# or-clock_main.net
KiCad netlist of a schematic drawn in EAGLE
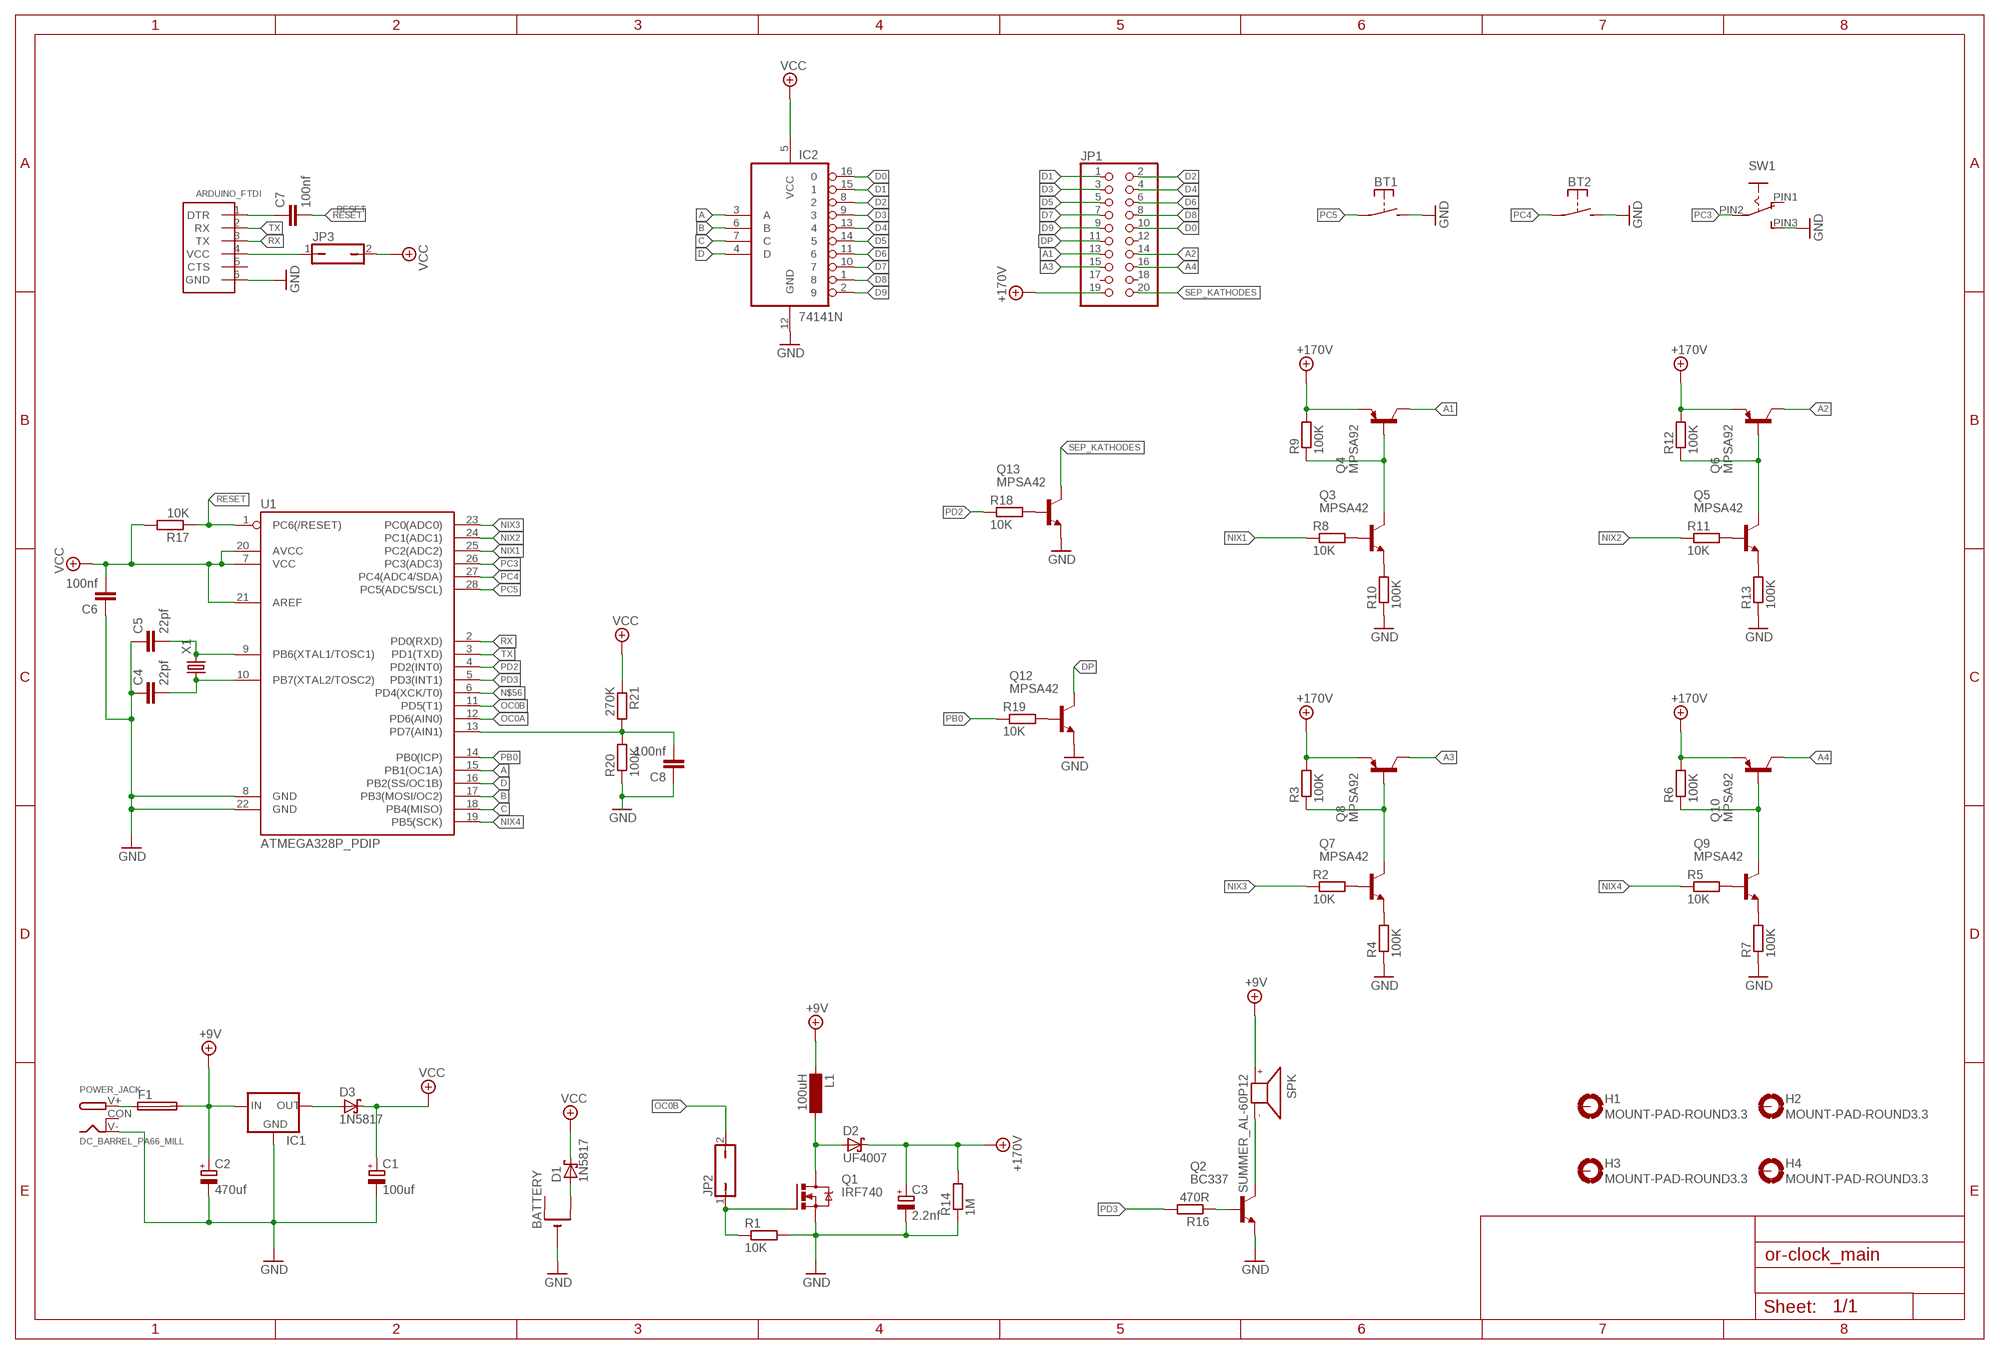
[diagram p0: schematic, sheet 1]

(export (version "E")
  (design (tool "Eeschema 10.0.6"))
  (components
    (comp (ref "BATTERY")
      (value "CR1220THM")
      (footprint "eagle-import:CR1220-THM")
      (libsource (lib "eagle-import") (part "CR1220THM"))
    )
    (comp (ref "BT1")
      (value "SWITCH_3305D")
      (footprint "eagle-import:BUT3305D")
      (libsource (lib "eagle-import") (part "SWITCH_3305D"))
    )
    (comp (ref "BT2")
      (value "SWITCH_3305D")
      (footprint "eagle-import:BUT3305D")
      (libsource (lib "eagle-import") (part "SWITCH_3305D"))
    )
    (comp (ref "C1")
      (value "100uf")
      (footprint "eagle-import:E5-6")
      (libsource (lib "eagle-import") (part "CPOL-EUE5-6"))
    )
    (comp (ref "C2")
      (value "470uf")
      (footprint "eagle-import:E5-10,5")
      (libsource (lib "eagle-import") (part "CPOL-EUE5-10.5"))
    )
    (comp (ref "C3")
      (value "2.2nf")
      (footprint "eagle-import:E5-8,5")
      (libsource (lib "eagle-import") (part "CPOL-EUE5-8.5"))
    )
    (comp (ref "C4")
      (value "22pf")
      (footprint "eagle-import:C025-025X050")
      (libsource (lib "eagle-import") (part "C-EU025-025X050"))
    )
    (comp (ref "C5")
      (value "22pf")
      (footprint "eagle-import:C025-025X050")
      (libsource (lib "eagle-import") (part "C-EU025-025X050"))
    )
    (comp (ref "C6")
      (value "100nf")
      (footprint "eagle-import:C025-025X050")
      (libsource (lib "eagle-import") (part "C-EU025-025X050"))
    )
    (comp (ref "C7")
      (value "100nf")
      (footprint "eagle-import:C025-025X050")
      (libsource (lib "eagle-import") (part "C-EU025-025X050"))
    )
    (comp (ref "C8")
      (value "100nf")
      (footprint "eagle-import:C025-025X050")
      (libsource (lib "eagle-import") (part "C-EU025-025X050"))
    )
    (comp (ref "D1")
      (value "1N5817")
      (footprint "eagle-import:DO41-7.6")
      (libsource (lib "eagle-import") (part "1N5817-B"))
    )
    (comp (ref "D2")
      (value "UF4007")
      (footprint "eagle-import:DO41-7.6")
      (libsource (lib "eagle-import") (part "1N5817-B"))
    )
    (comp (ref "D3")
      (value "1N5817")
      (footprint "eagle-import:DO41-7.6")
      (libsource (lib "eagle-import") (part "1N5817-B"))
    )
    (comp (ref "F1")
      (value "LITTLEFUSE")
      (footprint "eagle-import:LITTLEFUSE")
      (libsource (lib "eagle-import") (part "LITTLEFUSE"))
    )
    (comp (ref "H1")
      (value "MOUNT-PAD-ROUND3.3")
      (footprint "eagle-import:3,3-PAD")
      (libsource (lib "eagle-import") (part "MOUNT-PAD-ROUND3.3"))
    )
    (comp (ref "H2")
      (value "MOUNT-PAD-ROUND3.3")
      (footprint "eagle-import:3,3-PAD")
      (libsource (lib "eagle-import") (part "MOUNT-PAD-ROUND3.3"))
    )
    (comp (ref "H3")
      (value "MOUNT-PAD-ROUND3.3")
      (footprint "eagle-import:3,3-PAD")
      (libsource (lib "eagle-import") (part "MOUNT-PAD-ROUND3.3"))
    )
    (comp (ref "H4")
      (value "MOUNT-PAD-ROUND3.3")
      (footprint "eagle-import:3,3-PAD")
      (libsource (lib "eagle-import") (part "MOUNT-PAD-ROUND3.3"))
    )
    (comp (ref "IC1")
      (value "78XXS")
      (footprint "eagle-import:78XXS")
      (libsource (lib "eagle-import") (part "78XXS"))
    )
    (comp (ref "IC2")
      (value "74141N")
      (footprint "eagle-import:DIL16")
      (libsource (lib "eagle-import") (part "74141N"))
    )
    (comp (ref "JP1")
      (value "PINHD-2X10_FEMALE")
      (footprint "eagle-import:2X10")
      (libsource (lib "eagle-import") (part "PINHD-2X10_FEMALE"))
    )
    (comp (ref "JP2")
      (value "JP1Q")
      (footprint "eagle-import:JP1")
      (libsource (lib "eagle-import") (part "JP1Q"))
    )
    (comp (ref "JP3")
      (value "JP1Q")
      (footprint "eagle-import:JP1")
      (libsource (lib "eagle-import") (part "JP1Q"))
    )
    (comp (ref "L1")
      (value "100uH")
      (footprint "eagle-import:BS11")
      (libsource (lib "eagle-import") (part "BS11"))
    )
    (comp (ref "POWER_JACK")
      (value "DC_BARREL_PA66_MILL")
      (footprint "eagle-import:PA66_DC_JACK_MILL")
      (libsource (lib "eagle-import") (part "DC_BARREL_PA66_MILL"))
    )
    (comp (ref "Q1")
      (value "IRF740")
      (footprint "eagle-import:TO220BV")
      (libsource (lib "eagle-import") (part "IRF740"))
    )
    (comp (ref "Q2")
      (value "BC337")
      (footprint "eagle-import:TO92-")
      (libsource (lib "eagle-import") (part "BC547TO92_STRAIT"))
    )
    (comp (ref "Q3")
      (value "MPSA42")
      (footprint "eagle-import:TO92-")
      (libsource (lib "eagle-import") (part "MPSA42"))
    )
    (comp (ref "Q4")
      (value "MPSA92")
      (footprint "eagle-import:TO92-")
      (libsource (lib "eagle-import") (part "MPSA92"))
    )
    (comp (ref "Q5")
      (value "MPSA42")
      (footprint "eagle-import:TO92-")
      (libsource (lib "eagle-import") (part "MPSA42"))
    )
    (comp (ref "Q6")
      (value "MPSA92")
      (footprint "eagle-import:TO92-")
      (libsource (lib "eagle-import") (part "MPSA92"))
    )
    (comp (ref "Q7")
      (value "MPSA42")
      (footprint "eagle-import:TO92-")
      (libsource (lib "eagle-import") (part "MPSA42"))
    )
    (comp (ref "Q8")
      (value "MPSA92")
      (footprint "eagle-import:TO92-")
      (libsource (lib "eagle-import") (part "MPSA92"))
    )
    (comp (ref "Q9")
      (value "MPSA42")
      (footprint "eagle-import:TO92-")
      (libsource (lib "eagle-import") (part "MPSA42"))
    )
    (comp (ref "Q10")
      (value "MPSA92")
      (footprint "eagle-import:TO92-")
      (libsource (lib "eagle-import") (part "MPSA92"))
    )
    (comp (ref "Q12")
      (value "MPSA42")
      (footprint "eagle-import:TO92-")
      (libsource (lib "eagle-import") (part "MPSA42"))
    )
    (comp (ref "Q13")
      (value "MPSA42")
      (footprint "eagle-import:TO92-")
      (libsource (lib "eagle-import") (part "MPSA42"))
    )
    (comp (ref "R1")
      (value "10K")
      (footprint "eagle-import:0207_2V")
      (libsource (lib "eagle-import") (part "R-EU_0207/2V"))
    )
    (comp (ref "R2")
      (value "10K")
      (footprint "eagle-import:0207_2V")
      (libsource (lib "eagle-import") (part "R-EU_0207/2V"))
    )
    (comp (ref "R3")
      (value "100K")
      (footprint "eagle-import:0207_2V")
      (libsource (lib "eagle-import") (part "R-EU_0207/2V"))
    )
    (comp (ref "R4")
      (value "100K")
      (footprint "eagle-import:0207_2V")
      (libsource (lib "eagle-import") (part "R-EU_0207/2V"))
    )
    (comp (ref "R5")
      (value "10K")
      (footprint "eagle-import:0207_2V")
      (libsource (lib "eagle-import") (part "R-EU_0207/2V"))
    )
    (comp (ref "R6")
      (value "100K")
      (footprint "eagle-import:0207_2V")
      (libsource (lib "eagle-import") (part "R-EU_0207/2V"))
    )
    (comp (ref "R7")
      (value "100K")
      (footprint "eagle-import:0207_2V")
      (libsource (lib "eagle-import") (part "R-EU_0207/2V"))
    )
    (comp (ref "R8")
      (value "10K")
      (footprint "eagle-import:0207_2V")
      (libsource (lib "eagle-import") (part "R-EU_0207/2V"))
    )
    (comp (ref "R9")
      (value "100K")
      (footprint "eagle-import:0207_2V")
      (libsource (lib "eagle-import") (part "R-EU_0207/2V"))
    )
    (comp (ref "R10")
      (value "100K")
      (footprint "eagle-import:0207_2V")
      (libsource (lib "eagle-import") (part "R-EU_0207/2V"))
    )
    (comp (ref "R11")
      (value "10K")
      (footprint "eagle-import:0207_2V")
      (libsource (lib "eagle-import") (part "R-EU_0207/2V"))
    )
    (comp (ref "R12")
      (value "100K")
      (footprint "eagle-import:0207_2V")
      (libsource (lib "eagle-import") (part "R-EU_0207/2V"))
    )
    (comp (ref "R13")
      (value "100K")
      (footprint "eagle-import:0207_2V")
      (libsource (lib "eagle-import") (part "R-EU_0207/2V"))
    )
    (comp (ref "R14")
      (value "1M")
      (footprint "eagle-import:0207_7")
      (libsource (lib "eagle-import") (part "R-EU_0207/7"))
    )
    (comp (ref "R16")
      (value "470R")
      (footprint "eagle-import:0207_2V")
      (libsource (lib "eagle-import") (part "R-EU_0207/2V"))
    )
    (comp (ref "R17")
      (value "10K")
      (footprint "eagle-import:0207_2V")
      (libsource (lib "eagle-import") (part "R-EU_0207/2V"))
    )
    (comp (ref "R18")
      (value "10K")
      (footprint "eagle-import:0207_2V")
      (libsource (lib "eagle-import") (part "R-EU_0207/2V"))
    )
    (comp (ref "R19")
      (value "10K")
      (footprint "eagle-import:0207_2V")
      (libsource (lib "eagle-import") (part "R-EU_0207/2V"))
    )
    (comp (ref "R20")
      (value "100K")
      (footprint "eagle-import:0207_2V")
      (libsource (lib "eagle-import") (part "R-EU_0207/2V"))
    )
    (comp (ref "R21")
      (value "270K")
      (footprint "eagle-import:0207_2V")
      (libsource (lib "eagle-import") (part "R-EU_0207/2V"))
    )
    (comp (ref "SERIAL_CON")
      (value "ARDUINO_FTDI_HEADERV")
      (footprint "eagle-import:1X06")
      (libsource (lib "eagle-import") (part "ARDUINO_FTDI_HEADERV"))
    )
    (comp (ref "SPK")
      (value "SUMMER_AL-60P12")
      (footprint "eagle-import:AL-60P12_SUMMER")
      (libsource (lib "eagle-import") (part "SUMMER_AL-60P12"))
    )
    (comp (ref "SW1")
      (value "13P_SW")
      (footprint "eagle-import:TS-13P")
      (libsource (lib "eagle-import") (part "13P_SW"))
    )
    (comp (ref "U1")
      (value "ATMEGA328P_PDIP")
      (footprint "eagle-import:DIL28-3")
      (libsource (lib "eagle-import") (part "ATMEGA328P_PDIP"))
    )
    (comp (ref "X1")
      (value "CRYSTALTC26V")
      (footprint "eagle-import:TC26V")
      (libsource (lib "eagle-import") (part "CRYSTALTC26V"))
    )
  )
  (nets
    (net (code "1") (name "+9V") (class "Default")
      (node (ref "C2") (pin "+") (pinfunction "+_+") (pintype "passive"))
      (node (ref "F1") (pin "2") (pinfunction "2_2") (pintype "passive"))
      (node (ref "IC1") (pin "IN") (pinfunction "IN_IN") (pintype "input"))
      (node (ref "L1") (pin "1") (pinfunction "1_1") (pintype "passive"))
      (node (ref "SPK") (pin "POS") (pinfunction "+_POS") (pintype "passive"))
    )
    (net (code "2") (name "+170V") (class "Default")
      (node (ref "C3") (pin "+") (pinfunction "+_+") (pintype "passive"))
      (node (ref "D2") (pin "C") (pinfunction "C_C") (pintype "passive"))
      (node (ref "JP1") (pin "19") (pinfunction "19_19") (pintype "passive"))
      (node (ref "Q10") (pin "3") (pinfunction "E_3") (pintype "passive"))
      (node (ref "Q4") (pin "3") (pinfunction "E_3") (pintype "passive"))
      (node (ref "Q6") (pin "3") (pinfunction "E_3") (pintype "passive"))
      (node (ref "Q8") (pin "3") (pinfunction "E_3") (pintype "passive"))
      (node (ref "R12") (pin "2") (pinfunction "2_2") (pintype "passive"))
      (node (ref "R14") (pin "2") (pinfunction "2_2") (pintype "passive"))
      (node (ref "R3") (pin "2") (pinfunction "2_2") (pintype "passive"))
      (node (ref "R6") (pin "2") (pinfunction "2_2") (pintype "passive"))
      (node (ref "R9") (pin "2") (pinfunction "2_2") (pintype "passive"))
    )
    (net (code "3") (name "/GNDBREAK") (class "Default")
      (node (ref "POWER_JACK") (pin "CON") (pinfunction "GNDBREAK_CON") (pintype "power_in"))
    )
    (net (code "4") (name "A") (class "Default")
      (node (ref "IC2") (pin "3") (pinfunction "A_3") (pintype "input"))
      (node (ref "U1") (pin "15") (pinfunction "PB1(OC1A)_15") (pintype "bidirectional"))
    )
    (net (code "5") (name "A1") (class "Default")
      (node (ref "JP1") (pin "13") (pinfunction "13_13") (pintype "passive"))
      (node (ref "Q4") (pin "1") (pinfunction "C_1") (pintype "passive"))
    )
    (net (code "6") (name "A2") (class "Default")
      (node (ref "JP1") (pin "14") (pinfunction "14_14") (pintype "passive"))
      (node (ref "Q6") (pin "1") (pinfunction "C_1") (pintype "passive"))
    )
    (net (code "7") (name "A3") (class "Default")
      (node (ref "JP1") (pin "15") (pinfunction "15_15") (pintype "passive"))
      (node (ref "Q8") (pin "1") (pinfunction "C_1") (pintype "passive"))
    )
    (net (code "8") (name "A4") (class "Default")
      (node (ref "JP1") (pin "16") (pinfunction "16_16") (pintype "passive"))
      (node (ref "Q10") (pin "1") (pinfunction "C_1") (pintype "passive"))
    )
    (net (code "9") (name "B") (class "Default")
      (node (ref "IC2") (pin "6") (pinfunction "B_6") (pintype "input"))
      (node (ref "U1") (pin "17") (pinfunction "PB3(MOSI/OC2)_17") (pintype "bidirectional"))
    )
    (net (code "10") (name "C") (class "Default")
      (node (ref "IC2") (pin "7") (pinfunction "C_7") (pintype "input"))
      (node (ref "U1") (pin "18") (pinfunction "PB4(MISO)_18") (pintype "bidirectional"))
    )
    (net (code "11") (name "D") (class "Default")
      (node (ref "IC2") (pin "4") (pinfunction "D_4") (pintype "input"))
      (node (ref "U1") (pin "16") (pinfunction "PB2(SS/OC1B)_16") (pintype "bidirectional"))
    )
    (net (code "12") (name "D0") (class "Default")
      (node (ref "IC2") (pin "16") (pinfunction "0_16") (pintype "open_collector"))
      (node (ref "JP1") (pin "10") (pinfunction "10_10") (pintype "passive"))
    )
    (net (code "13") (name "D1") (class "Default")
      (node (ref "IC2") (pin "15") (pinfunction "1_15") (pintype "open_collector"))
      (node (ref "JP1") (pin "1") (pinfunction "1_1") (pintype "passive"))
    )
    (net (code "14") (name "D2") (class "Default")
      (node (ref "IC2") (pin "8") (pinfunction "2_8") (pintype "open_collector"))
      (node (ref "JP1") (pin "2") (pinfunction "2_2") (pintype "passive"))
    )
    (net (code "15") (name "D3") (class "Default")
      (node (ref "IC2") (pin "9") (pinfunction "3_9") (pintype "open_collector"))
      (node (ref "JP1") (pin "3") (pinfunction "3_3") (pintype "passive"))
    )
    (net (code "16") (name "D4") (class "Default")
      (node (ref "IC2") (pin "13") (pinfunction "4_13") (pintype "open_collector"))
      (node (ref "JP1") (pin "4") (pinfunction "4_4") (pintype "passive"))
    )
    (net (code "17") (name "D5") (class "Default")
      (node (ref "IC2") (pin "14") (pinfunction "5_14") (pintype "open_collector"))
      (node (ref "JP1") (pin "5") (pinfunction "5_5") (pintype "passive"))
    )
    (net (code "18") (name "D6") (class "Default")
      (node (ref "IC2") (pin "11") (pinfunction "6_11") (pintype "open_collector"))
      (node (ref "JP1") (pin "6") (pinfunction "6_6") (pintype "passive"))
    )
    (net (code "19") (name "D7") (class "Default")
      (node (ref "IC2") (pin "10") (pinfunction "7_10") (pintype "open_collector"))
      (node (ref "JP1") (pin "7") (pinfunction "7_7") (pintype "passive"))
    )
    (net (code "20") (name "D8") (class "Default")
      (node (ref "IC2") (pin "1") (pinfunction "8_1") (pintype "open_collector"))
      (node (ref "JP1") (pin "8") (pinfunction "8_8") (pintype "passive"))
    )
    (net (code "21") (name "D9") (class "Default")
      (node (ref "IC2") (pin "2") (pinfunction "9_2") (pintype "open_collector"))
      (node (ref "JP1") (pin "9") (pinfunction "9_9") (pintype "passive"))
    )
    (net (code "22") (name "DP") (class "Default")
      (node (ref "JP1") (pin "11") (pinfunction "11_11") (pintype "passive"))
      (node (ref "Q12") (pin "1") (pinfunction "C_1") (pintype "passive"))
    )
    (net (code "23") (name "GND") (class "Default")
      (node (ref "BATTERY") (pin "-") (pinfunction "-_-") (pintype "passive"))
      (node (ref "BT1") (pin "P$2") (pinfunction "S_P$2") (pintype "passive"))
      (node (ref "BT2") (pin "P$2") (pinfunction "S_P$2") (pintype "passive"))
      (node (ref "C1") (pin "-") (pinfunction "-_-") (pintype "passive"))
      (node (ref "C2") (pin "-") (pinfunction "-_-") (pintype "passive"))
      (node (ref "C3") (pin "-") (pinfunction "-_-") (pintype "passive"))
      (node (ref "C4") (pin "1") (pinfunction "1_1") (pintype "passive"))
      (node (ref "C5") (pin "1") (pinfunction "1_1") (pintype "passive"))
      (node (ref "C6") (pin "1") (pinfunction "1_1") (pintype "passive"))
      (node (ref "C8") (pin "1") (pinfunction "1_1") (pintype "passive"))
      (node (ref "IC1") (pin "GND") (pinfunction "GND_GND") (pintype "input"))
      (node (ref "IC2") (pin "12") (pinfunction "GND_12") (pintype "power_in"))
      (node (ref "POWER_JACK") (pin "V-") (pinfunction "GND_V-") (pintype "power_in"))
      (node (ref "Q1") (pin "S") (pinfunction "S_S") (pintype "passive"))
      (node (ref "Q12") (pin "3") (pinfunction "E_3") (pintype "passive"))
      (node (ref "Q13") (pin "3") (pinfunction "E_3") (pintype "passive"))
      (node (ref "Q2") (pin "1") (pinfunction "E_1") (pintype "passive"))
      (node (ref "R1") (pin "2") (pinfunction "2_2") (pintype "passive"))
      (node (ref "R10") (pin "1") (pinfunction "1_1") (pintype "passive"))
      (node (ref "R13") (pin "1") (pinfunction "1_1") (pintype "passive"))
      (node (ref "R14") (pin "1") (pinfunction "1_1") (pintype "passive"))
      (node (ref "R20") (pin "1") (pinfunction "1_1") (pintype "passive"))
      (node (ref "R4") (pin "1") (pinfunction "1_1") (pintype "passive"))
      (node (ref "R7") (pin "1") (pinfunction "1_1") (pintype "passive"))
      (node (ref "SERIAL_CON") (pin "6") (pinfunction "GND_6") (pintype "bidirectional"))
      (node (ref "SW1") (pin "PIN3") (pinfunction "S_PIN3") (pintype "passive"))
      (node (ref "U1") (pin "22") (pinfunction "GND_22") (pintype "bidirectional"))
      (node (ref "U1") (pin "8") (pinfunction "GND_8") (pintype "bidirectional"))
    )
    (net (code "24") (name "N$56") (class "Default")
      (node (ref "U1") (pin "6") (pinfunction "PD4(XCK/T0)_6") (pintype "bidirectional"))
    )
    (net (code "25") (name "NIX1") (class "Default")
      (node (ref "R8") (pin "1") (pinfunction "1_1") (pintype "passive"))
      (node (ref "U1") (pin "25") (pinfunction "PC2(ADC2)_25") (pintype "bidirectional"))
    )
    (net (code "26") (name "NIX2") (class "Default")
      (node (ref "R11") (pin "1") (pinfunction "1_1") (pintype "passive"))
      (node (ref "U1") (pin "24") (pinfunction "PC1(ADC1)_24") (pintype "bidirectional"))
    )
    (net (code "27") (name "NIX3") (class "Default")
      (node (ref "R2") (pin "1") (pinfunction "1_1") (pintype "passive"))
      (node (ref "U1") (pin "23") (pinfunction "PC0(ADC0)_23") (pintype "bidirectional"))
    )
    (net (code "28") (name "NIX4") (class "Default")
      (node (ref "R5") (pin "1") (pinfunction "1_1") (pintype "passive"))
      (node (ref "U1") (pin "19") (pinfunction "PB5(SCK)_19") (pintype "bidirectional"))
    )
    (net (code "29") (name "Net-(BATTERY-+1)") (class "Default")
      (node (ref "BATTERY") (pin "+2") (pinfunction "+1_+2") (pintype "passive"))
      (node (ref "D1") (pin "A") (pinfunction "A_A") (pintype "passive"))
    )
    (net (code "30") (name "Net-(D2-PadA)") (class "Default")
      (node (ref "D2") (pin "A") (pinfunction "A_A") (pintype "passive"))
      (node (ref "L1") (pin "2") (pinfunction "2_2") (pintype "passive"))
      (node (ref "Q1") (pin "D") (pinfunction "D_D") (pintype "passive"))
    )
    (net (code "31") (name "Net-(D3-PadA)") (class "Default")
      (node (ref "D3") (pin "A") (pinfunction "A_A") (pintype "passive"))
      (node (ref "IC1") (pin "OUT") (pinfunction "OUT_OUT") (pintype "passive"))
    )
    (net (code "32") (name "Net-(JP2-Pad1)") (class "Default")
      (node (ref "JP2") (pin "1") (pinfunction "1_1") (pintype "passive"))
      (node (ref "Q1") (pin "G") (pinfunction "G_G") (pintype "passive"))
      (node (ref "R1") (pin "1") (pinfunction "1_1") (pintype "passive"))
    )
    (net (code "33") (name "Net-(POWER_JACK-PWR)") (class "Default")
      (node (ref "F1") (pin "1") (pinfunction "1_1") (pintype "passive"))
      (node (ref "POWER_JACK") (pin "V+") (pinfunction "PWR_V+") (pintype "power_in"))
    )
    (net (code "34") (name "Net-(Q2-B)") (class "Default")
      (node (ref "Q2") (pin "2") (pinfunction "B_2") (pintype "passive"))
      (node (ref "R16") (pin "1") (pinfunction "1_1") (pintype "passive"))
    )
    (net (code "35") (name "Net-(Q2-C)") (class "Default")
      (node (ref "Q2") (pin "3") (pinfunction "C_3") (pintype "passive"))
      (node (ref "SPK") (pin "NEG") (pinfunction "-_NEG") (pintype "passive"))
    )
    (net (code "36") (name "Net-(Q3-B)") (class "Default")
      (node (ref "Q3") (pin "2") (pinfunction "B_2") (pintype "passive"))
      (node (ref "R8") (pin "2") (pinfunction "2_2") (pintype "passive"))
    )
    (net (code "37") (name "Net-(Q3-C)") (class "Default")
      (node (ref "Q3") (pin "1") (pinfunction "C_1") (pintype "passive"))
      (node (ref "Q4") (pin "2") (pinfunction "B_2") (pintype "passive"))
      (node (ref "R9") (pin "1") (pinfunction "1_1") (pintype "passive"))
    )
    (net (code "38") (name "Net-(Q3-E)") (class "Default")
      (node (ref "Q3") (pin "3") (pinfunction "E_3") (pintype "passive"))
      (node (ref "R10") (pin "2") (pinfunction "2_2") (pintype "passive"))
    )
    (net (code "39") (name "Net-(Q5-B)") (class "Default")
      (node (ref "Q5") (pin "2") (pinfunction "B_2") (pintype "passive"))
      (node (ref "R11") (pin "2") (pinfunction "2_2") (pintype "passive"))
    )
    (net (code "40") (name "Net-(Q5-C)") (class "Default")
      (node (ref "Q5") (pin "1") (pinfunction "C_1") (pintype "passive"))
      (node (ref "Q6") (pin "2") (pinfunction "B_2") (pintype "passive"))
      (node (ref "R12") (pin "1") (pinfunction "1_1") (pintype "passive"))
    )
    (net (code "41") (name "Net-(Q5-E)") (class "Default")
      (node (ref "Q5") (pin "3") (pinfunction "E_3") (pintype "passive"))
      (node (ref "R13") (pin "2") (pinfunction "2_2") (pintype "passive"))
    )
    (net (code "42") (name "Net-(Q7-B)") (class "Default")
      (node (ref "Q7") (pin "2") (pinfunction "B_2") (pintype "passive"))
      (node (ref "R2") (pin "2") (pinfunction "2_2") (pintype "passive"))
    )
    (net (code "43") (name "Net-(Q7-C)") (class "Default")
      (node (ref "Q7") (pin "1") (pinfunction "C_1") (pintype "passive"))
      (node (ref "Q8") (pin "2") (pinfunction "B_2") (pintype "passive"))
      (node (ref "R3") (pin "1") (pinfunction "1_1") (pintype "passive"))
    )
    (net (code "44") (name "Net-(Q7-E)") (class "Default")
      (node (ref "Q7") (pin "3") (pinfunction "E_3") (pintype "passive"))
      (node (ref "R4") (pin "2") (pinfunction "2_2") (pintype "passive"))
    )
    (net (code "45") (name "Net-(Q9-B)") (class "Default")
      (node (ref "Q9") (pin "2") (pinfunction "B_2") (pintype "passive"))
      (node (ref "R5") (pin "2") (pinfunction "2_2") (pintype "passive"))
    )
    (net (code "46") (name "Net-(Q9-E)") (class "Default")
      (node (ref "Q9") (pin "3") (pinfunction "E_3") (pintype "passive"))
      (node (ref "R7") (pin "2") (pinfunction "2_2") (pintype "passive"))
    )
    (net (code "47") (name "Net-(Q10-B)") (class "Default")
      (node (ref "Q10") (pin "2") (pinfunction "B_2") (pintype "passive"))
      (node (ref "Q9") (pin "1") (pinfunction "C_1") (pintype "passive"))
      (node (ref "R6") (pin "1") (pinfunction "1_1") (pintype "passive"))
    )
    (net (code "48") (name "Net-(Q12-B)") (class "Default")
      (node (ref "Q12") (pin "2") (pinfunction "B_2") (pintype "passive"))
      (node (ref "R19") (pin "2") (pinfunction "2_2") (pintype "passive"))
    )
    (net (code "49") (name "Net-(Q13-B)") (class "Default")
      (node (ref "Q13") (pin "2") (pinfunction "B_2") (pintype "passive"))
      (node (ref "R18") (pin "2") (pinfunction "2_2") (pintype "passive"))
    )
    (net (code "50") (name "Net-(SERIAL_CON-DTR)") (class "Default")
      (node (ref "C7") (pin "1") (pinfunction "1_1") (pintype "passive"))
      (node (ref "SERIAL_CON") (pin "1") (pinfunction "DTR_1") (pintype "bidirectional"))
    )
    (net (code "51") (name "Net-(SERIAL_CON-VCC)") (class "Default")
      (node (ref "JP3") (pin "1") (pinfunction "1_1") (pintype "passive"))
      (node (ref "SERIAL_CON") (pin "4") (pinfunction "VCC_4") (pintype "bidirectional"))
    )
    (net (code "52") (name "Net-(U1-PB6(XTAL1{slash}TOSC1))") (class "Default")
      (node (ref "C5") (pin "2") (pinfunction "2_2") (pintype "passive"))
      (node (ref "U1") (pin "9") (pinfunction "PB6(XTAL1/TOSC1)_9") (pintype "bidirectional"))
      (node (ref "X1") (pin "2") (pinfunction "2_2") (pintype "passive"))
    )
    (net (code "53") (name "Net-(U1-PB7(XTAL2{slash}TOSC2))") (class "Default")
      (node (ref "C4") (pin "2") (pinfunction "2_2") (pintype "passive"))
      (node (ref "U1") (pin "10") (pinfunction "PB7(XTAL2/TOSC2)_10") (pintype "bidirectional"))
      (node (ref "X1") (pin "1") (pinfunction "1_1") (pintype "passive"))
    )
    (net (code "54") (name "Net-(U1-PD7(AIN1))") (class "Default")
      (node (ref "C8") (pin "2") (pinfunction "2_2") (pintype "passive"))
      (node (ref "R20") (pin "2") (pinfunction "2_2") (pintype "passive"))
      (node (ref "R21") (pin "2") (pinfunction "2_2") (pintype "passive"))
      (node (ref "U1") (pin "13") (pinfunction "PD7(AIN1)_13") (pintype "bidirectional"))
    )
    (net (code "55") (name "OC0A") (class "Default")
      (node (ref "U1") (pin "12") (pinfunction "PD6(AIN0)_12") (pintype "bidirectional"))
    )
    (net (code "56") (name "OC0B") (class "Default")
      (node (ref "JP2") (pin "2") (pinfunction "2_2") (pintype "passive"))
      (node (ref "U1") (pin "11") (pinfunction "PD5(T1)_11") (pintype "bidirectional"))
    )
    (net (code "57") (name "PB0") (class "Default")
      (node (ref "R19") (pin "1") (pinfunction "1_1") (pintype "passive"))
      (node (ref "U1") (pin "14") (pinfunction "PB0(ICP)_14") (pintype "bidirectional"))
    )
    (net (code "58") (name "PC3") (class "Default")
      (node (ref "SW1") (pin "PIN2") (pinfunction "P_PIN2") (pintype "passive"))
      (node (ref "U1") (pin "26") (pinfunction "PC3(ADC3)_26") (pintype "bidirectional"))
    )
    (net (code "59") (name "PC4") (class "Default")
      (node (ref "BT2") (pin "P$1") (pinfunction "P_P$1") (pintype "passive"))
      (node (ref "U1") (pin "27") (pinfunction "PC4(ADC4/SDA)_27") (pintype "bidirectional"))
    )
    (net (code "60") (name "PC5") (class "Default")
      (node (ref "BT1") (pin "P$1") (pinfunction "P_P$1") (pintype "passive"))
      (node (ref "U1") (pin "28") (pinfunction "PC5(ADC5/SCL)_28") (pintype "bidirectional"))
    )
    (net (code "61") (name "PD2") (class "Default")
      (node (ref "R18") (pin "1") (pinfunction "1_1") (pintype "passive"))
      (node (ref "U1") (pin "4") (pinfunction "PD2(INT0)_4") (pintype "bidirectional"))
    )
    (net (code "62") (name "PD3") (class "Default")
      (node (ref "R16") (pin "2") (pinfunction "2_2") (pintype "passive"))
      (node (ref "U1") (pin "5") (pinfunction "PD3(INT1)_5") (pintype "bidirectional"))
    )
    (net (code "63") (name "RESET") (class "Default")
      (node (ref "C7") (pin "2") (pinfunction "2_2") (pintype "passive"))
      (node (ref "R17") (pin "1") (pinfunction "1_1") (pintype "passive"))
      (node (ref "U1") (pin "1") (pinfunction "PC6(/RESET)_1") (pintype "bidirectional"))
    )
    (net (code "64") (name "RX") (class "Default")
      (node (ref "SERIAL_CON") (pin "3") (pinfunction "TX_3") (pintype "bidirectional"))
      (node (ref "U1") (pin "2") (pinfunction "PD0(RXD)_2") (pintype "bidirectional"))
    )
    (net (code "65") (name "SEP_KATHODES") (class "Default")
      (node (ref "JP1") (pin "20") (pinfunction "20_20") (pintype "passive"))
      (node (ref "Q13") (pin "1") (pinfunction "C_1") (pintype "passive"))
    )
    (net (code "66") (name "TX") (class "Default")
      (node (ref "SERIAL_CON") (pin "2") (pinfunction "RX_2") (pintype "bidirectional"))
      (node (ref "U1") (pin "3") (pinfunction "PD1(TXD)_3") (pintype "bidirectional"))
    )
    (net (code "67") (name "VCC") (class "Default")
      (node (ref "C1") (pin "+") (pinfunction "+_+") (pintype "passive"))
      (node (ref "C6") (pin "2") (pinfunction "2_2") (pintype "passive"))
      (node (ref "D1") (pin "C") (pinfunction "C_C") (pintype "passive"))
      (node (ref "D3") (pin "C") (pinfunction "C_C") (pintype "passive"))
      (node (ref "IC2") (pin "5") (pinfunction "VCC_5") (pintype "power_in"))
      (node (ref "JP3") (pin "2") (pinfunction "2_2") (pintype "passive"))
      (node (ref "R17") (pin "2") (pinfunction "2_2") (pintype "passive"))
      (node (ref "R21") (pin "1") (pinfunction "1_1") (pintype "passive"))
      (node (ref "U1") (pin "20") (pinfunction "AVCC_20") (pintype "bidirectional"))
      (node (ref "U1") (pin "21") (pinfunction "AREF_21") (pintype "bidirectional"))
      (node (ref "U1") (pin "7") (pinfunction "VCC_7") (pintype "bidirectional"))
    )
    (net (code "68") (name "unconnected-(BATTERY-+-Pad+1)") (class "Default")
      (node (ref "BATTERY") (pin "+1") (pinfunction "+_+1") (pintype "passive"))
    )
    (net (code "69") (name "unconnected-(H1-MOUNT-PadB3,3)") (class "Default")
      (node (ref "H1") (pin "B3,3") (pinfunction "MOUNT_B3,3") (pintype "passive"))
    )
    (net (code "70") (name "unconnected-(H2-MOUNT-PadB3,3)") (class "Default")
      (node (ref "H2") (pin "B3,3") (pinfunction "MOUNT_B3,3") (pintype "passive"))
    )
    (net (code "71") (name "unconnected-(H3-MOUNT-PadB3,3)") (class "Default")
      (node (ref "H3") (pin "B3,3") (pinfunction "MOUNT_B3,3") (pintype "passive"))
    )
    (net (code "72") (name "unconnected-(H4-MOUNT-PadB3,3)") (class "Default")
      (node (ref "H4") (pin "B3,3") (pinfunction "MOUNT_B3,3") (pintype "passive"))
    )
    (net (code "73") (name "unconnected-(JP1-Pad12)") (class "Default")
      (node (ref "JP1") (pin "12") (pinfunction "12_12") (pintype "passive"))
    )
    (net (code "74") (name "unconnected-(JP1-Pad17)") (class "Default")
      (node (ref "JP1") (pin "17") (pinfunction "17_17") (pintype "passive"))
    )
    (net (code "75") (name "unconnected-(JP1-Pad18)") (class "Default")
      (node (ref "JP1") (pin "18") (pinfunction "18_18") (pintype "passive"))
    )
    (net (code "76") (name "unconnected-(SERIAL_CON-CTS-Pad5)") (class "Default")
      (node (ref "SERIAL_CON") (pin "5") (pinfunction "CTS_5") (pintype "bidirectional"))
    )
    (net (code "77") (name "unconnected-(SW1-O-PadPIN1)") (class "Default")
      (node (ref "SW1") (pin "PIN1") (pinfunction "O_PIN1") (pintype "passive"))
    )
  )
)
